# design.net
KiCad netlist of a schematic drawn in Altium Designer
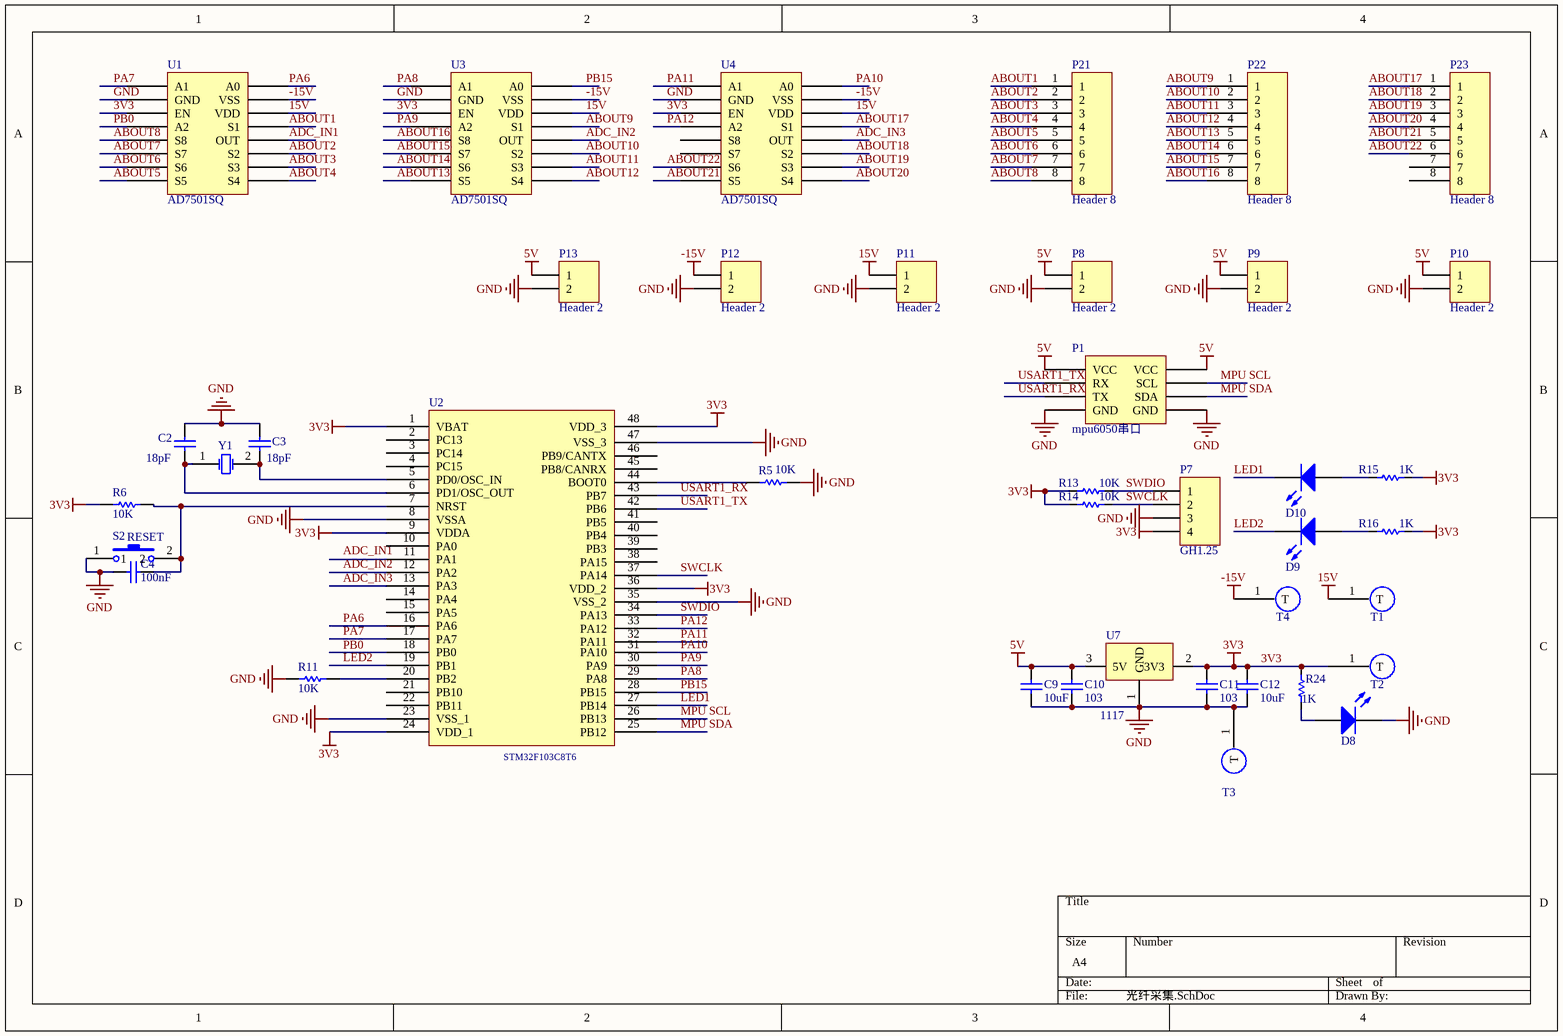
[diagram p0: 光纤采集.SchDoc]

(export (version "E")
  (design (tool "Eeschema 10.0.6"))
  (components
    (comp (ref "C2")
      (value "18pF")
      (footprint "0402")
      (description "Capacitor")
      (fields (field (name "Comment") "Cap") (field (name "PUBLISHER") "Altium Limited"))
      (libsource (lib "Miscellaneous Devices") (part "Cap"))
    )
    (comp (ref "C3")
      (value "18pF")
      (footprint "0402")
      (description "Capacitor")
      (fields (field (name "Comment") "Cap") (field (name "PUBLISHER") "Altium Limited"))
      (libsource (lib "Miscellaneous Devices") (part "Cap"))
    )
    (comp (ref "C4")
      (value "100nF")
      (footprint "0402")
      (description "Capacitor")
      (fields (field (name "Comment") "Cap") (field (name "PUBLISHER") "Altium Limited"))
      (libsource (lib "Miscellaneous Devices") (part "Cap"))
    )
    (comp (ref "C9")
      (value "10uF")
      (footprint "0603-1")
      (description "无极性电容")
      (fields (field (name "PUBLISHER") "Altium Limited"))
      (libsource (lib "Devices") (part "Cap"))
    )
    (comp (ref "C10")
      (value "103")
      (footprint "0603-1")
      (description "无极性电容")
      (fields (field (name "PUBLISHER") "Altium Limited"))
      (libsource (lib "Devices") (part "Cap"))
    )
    (comp (ref "C11")
      (value "103")
      (footprint "0603-1")
      (description "无极性电容")
      (fields (field (name "PUBLISHER") "Altium Limited"))
      (libsource (lib "Devices") (part "Cap"))
    )
    (comp (ref "C12")
      (value "10uF")
      (footprint "0603-1")
      (description "无极性电容")
      (fields (field (name "PUBLISHER") "Altium Limited"))
      (libsource (lib "Devices") (part "Cap"))
    )
    (comp (ref "D8")
      (value "LED0")
      (footprint "0603-LED-1")
      (description "发光二极管")
      (fields (field (name "PUBLISHER") "Altium Limited"))
      (libsource (lib "Devices") (part "LED0"))
    )
    (comp (ref "D9")
      (value "LED0")
      (footprint "0603-LED-1")
      (description "发光二极管")
      (fields (field (name "PUBLISHER") "Altium Limited"))
      (libsource (lib "Devices") (part "LED0"))
    )
    (comp (ref "D10")
      (value "LED0")
      (footprint "0603-LED-1")
      (description "发光二极管")
      (fields (field (name "PUBLISHER") "Altium Limited"))
      (libsource (lib "Devices") (part "LED0"))
    )
    (comp (ref "P1") (value "mpu6050串口") (footprint "MPU6050") (libsource (lib "新云台") (part "mpu6050串口")))
    (comp (ref "P7")
      (value "GH1.25")
      (footprint "GH1.25_4P")
      (description "Header, 4-Pin")
      (fields (field (name "PUBLISHER") "Altium Limited"))
      (libsource (lib "继电器") (part "Header 4"))
    )
    (comp (ref "P8")
      (value "Header 2")
      (footprint "2.54x2")
      (description "Header, 2-Pin")
      (fields (field (name "PUBLISHER") "Altium Limited"))
      (libsource (lib "Miscellaneous Connectors") (part "Header 2"))
    )
    (comp (ref "P9")
      (value "Header 2")
      (footprint "2.54x2")
      (description "Header, 2-Pin")
      (fields (field (name "PUBLISHER") "Altium Limited"))
      (libsource (lib "Miscellaneous Connectors") (part "Header 2"))
    )
    (comp (ref "P10")
      (value "Header 2")
      (footprint "2.54x2")
      (description "Header, 2-Pin")
      (fields (field (name "PUBLISHER") "Altium Limited"))
      (libsource (lib "Miscellaneous Connectors") (part "Header 2"))
    )
    (comp (ref "P11")
      (value "Header 2")
      (footprint "2.54x2")
      (description "Header, 2-Pin")
      (fields (field (name "PUBLISHER") "Altium Limited"))
      (libsource (lib "Miscellaneous Connectors") (part "Header 2"))
    )
    (comp (ref "P12")
      (value "Header 2")
      (footprint "2.54x2")
      (description "Header, 2-Pin")
      (fields (field (name "PUBLISHER") "Altium Limited"))
      (libsource (lib "Miscellaneous Connectors") (part "Header 2"))
    )
    (comp (ref "P13")
      (value "Header 2")
      (footprint "2.54x2")
      (description "Header, 2-Pin")
      (fields (field (name "PUBLISHER") "Altium Limited"))
      (libsource (lib "Miscellaneous Connectors") (part "Header 2"))
    )
    (comp (ref "P21") (value "Header 8") (footprint "2.54x8") (libsource (lib "继电器") (part "Header 8")))
    (comp (ref "P22") (value "Header 8") (footprint "2.54x8") (libsource (lib "继电器") (part "Header 8")))
    (comp (ref "P23") (value "Header 8") (footprint "2.54x8") (libsource (lib "继电器") (part "Header 8")))
    (comp (ref "R5")
      (value "10K")
      (footprint "0402")
      (description "Semiconductor Resistor")
      (fields (field (name "Comment") "Res Semi") (field (name "PUBLISHER") "Altium Limited"))
      (libsource (lib "Miscellaneous Devices") (part "Res Semi"))
    )
    (comp (ref "R6")
      (value "10K")
      (footprint "0402")
      (description "Semiconductor Resistor")
      (fields (field (name "Comment") "Res Semi") (field (name "PUBLISHER") "Altium Limited"))
      (libsource (lib "Miscellaneous Devices") (part "Res Semi"))
    )
    (comp (ref "R11")
      (value "10K")
      (footprint "0402")
      (description "Semiconductor Resistor")
      (fields (field (name "Comment") "Res Semi") (field (name "PUBLISHER") "Altium Limited"))
      (libsource (lib "Miscellaneous Devices") (part "Res Semi"))
    )
    (comp (ref "R13")
      (value "10K")
      (footprint "0402")
      (description "贴片电阻")
      (fields (field (name "PUBLISHER") "Altium Limited"))
      (libsource (lib "继电器") (part "Res1"))
    )
    (comp (ref "R14")
      (value "10K")
      (footprint "0402")
      (description "贴片电阻")
      (fields (field (name "PUBLISHER") "Altium Limited"))
      (libsource (lib "继电器") (part "Res1"))
    )
    (comp (ref "R15")
      (value "1K")
      (footprint "0402")
      (description "贴片电阻")
      (fields (field (name "PUBLISHER") "Altium Limited"))
      (libsource (lib "继电器") (part "Res1"))
    )
    (comp (ref "R16")
      (value "1K")
      (footprint "0402")
      (description "贴片电阻")
      (fields (field (name "PUBLISHER") "Altium Limited"))
      (libsource (lib "继电器") (part "Res1"))
    )
    (comp (ref "R24")
      (value "1K")
      (footprint "0402")
      (description "贴片电阻")
      (fields (field (name "PUBLISHER") "Altium Limited"))
      (libsource (lib "Devices") (part "Res1"))
    )
    (comp (ref "S2")
      (value "RESET")
      (footprint "KEY 4P")
      (description "微动开关")
      (fields (field (name "PUBLISHER") "Altium Limited"))
      (libsource (lib "Devices") (part "SW-PB"))
    )
    (comp (ref "T1") (value "~") (footprint "Test") (libsource (lib "PTZ") (part "TEST")))
    (comp (ref "T2") (value "~") (footprint "Test") (libsource (lib "PTZ") (part "TEST")))
    (comp (ref "T3") (value "~") (footprint "Test") (libsource (lib "PTZ") (part "TEST")))
    (comp (ref "T4") (value "~") (footprint "Test") (libsource (lib "PTZ") (part "TEST")))
    (comp (ref "U1") (value "AD7501SQ") (footprint "DIP-16") (libsource (lib "新云台") (part "AD7501SQ")))
    (comp (ref "U2")
      (value "STM32F103C8T6")
      (footprint "LQFP48_stm32f103_")
      (libsource (lib "driver") (part "STM32F103C8T6"))
    )
    (comp (ref "U3") (value "AD7501SQ") (footprint "DIP-16") (libsource (lib "新云台") (part "AD7501SQ")))
    (comp (ref "U4") (value "AD7501SQ") (footprint "DIP-16") (libsource (lib "新云台") (part "AD7501SQ")))
    (comp (ref "U7")
      (value "1117")
      (footprint "SOT223_1117__")
      (libsource (lib "SHAWN") (part "AMS1117-3.3"))
    )
    (comp (ref "Y1")
      (value "XTAL")
      (footprint "XTAL5032")
      (description "Crystal Oscillator")
      (fields (field (name "PUBLISHER") "Altium Limited"))
      (libsource (lib "Miscellaneous Devices") (part "XTAL"))
    )
  )
  (nets
    (net (code "1") (name "-15V") (class "Default")
      (node (ref "P12") (pin "1") (pinfunction "1_1") (pintype "passive"))
      (node (ref "T4") (pin "1") (pinfunction "T_1") (pintype "passive"))
      (node (ref "U1") (pin "14") (pinfunction "VSS_14") (pintype "passive"))
      (node (ref "U3") (pin "14") (pinfunction "VSS_14") (pintype "passive"))
      (node (ref "U4") (pin "14") (pinfunction "VSS_14") (pintype "passive"))
    )
    (net (code "2") (name "/ABOUT1") (class "Default")
      (node (ref "P21") (pin "1") (pinfunction "1_1") (pintype "passive"))
      (node (ref "U1") (pin "12") (pinfunction "S1_12") (pintype "passive"))
    )
    (net (code "3") (name "/ABOUT2") (class "Default")
      (node (ref "P21") (pin "2") (pinfunction "2_2") (pintype "passive"))
      (node (ref "U1") (pin "11") (pinfunction "S2_11") (pintype "passive"))
    )
    (net (code "4") (name "/ABOUT3") (class "Default")
      (node (ref "P21") (pin "3") (pinfunction "3_3") (pintype "passive"))
      (node (ref "U1") (pin "10") (pinfunction "S3_10") (pintype "passive"))
    )
    (net (code "5") (name "/ABOUT4") (class "Default")
      (node (ref "P21") (pin "4") (pinfunction "4_4") (pintype "passive"))
      (node (ref "U1") (pin "9") (pinfunction "S4_9") (pintype "passive"))
    )
    (net (code "6") (name "/ABOUT5") (class "Default")
      (node (ref "P21") (pin "5") (pinfunction "5_5") (pintype "passive"))
      (node (ref "U1") (pin "8") (pinfunction "S5_8") (pintype "passive"))
    )
    (net (code "7") (name "/ABOUT6") (class "Default")
      (node (ref "P21") (pin "6") (pinfunction "6_6") (pintype "passive"))
      (node (ref "U1") (pin "7") (pinfunction "S6_7") (pintype "passive"))
    )
    (net (code "8") (name "/ABOUT7") (class "Default")
      (node (ref "P21") (pin "7") (pinfunction "7_7") (pintype "passive"))
      (node (ref "U1") (pin "6") (pinfunction "S7_6") (pintype "passive"))
    )
    (net (code "9") (name "/ABOUT8") (class "Default")
      (node (ref "P21") (pin "8") (pinfunction "8_8") (pintype "passive"))
      (node (ref "U1") (pin "5") (pinfunction "S8_5") (pintype "passive"))
    )
    (net (code "10") (name "/ABOUT9") (class "Default")
      (node (ref "P22") (pin "1") (pinfunction "1_1") (pintype "passive"))
      (node (ref "U3") (pin "12") (pinfunction "S1_12") (pintype "passive"))
    )
    (net (code "11") (name "/ABOUT10") (class "Default")
      (node (ref "P22") (pin "2") (pinfunction "2_2") (pintype "passive"))
      (node (ref "U3") (pin "11") (pinfunction "S2_11") (pintype "passive"))
    )
    (net (code "12") (name "/ABOUT11") (class "Default")
      (node (ref "P22") (pin "3") (pinfunction "3_3") (pintype "passive"))
      (node (ref "U3") (pin "10") (pinfunction "S3_10") (pintype "passive"))
    )
    (net (code "13") (name "/ABOUT12") (class "Default")
      (node (ref "P22") (pin "4") (pinfunction "4_4") (pintype "passive"))
      (node (ref "U3") (pin "9") (pinfunction "S4_9") (pintype "passive"))
    )
    (net (code "14") (name "/ABOUT13") (class "Default")
      (node (ref "P22") (pin "5") (pinfunction "5_5") (pintype "passive"))
      (node (ref "U3") (pin "8") (pinfunction "S5_8") (pintype "passive"))
    )
    (net (code "15") (name "/ABOUT14") (class "Default")
      (node (ref "P22") (pin "6") (pinfunction "6_6") (pintype "passive"))
      (node (ref "U3") (pin "7") (pinfunction "S6_7") (pintype "passive"))
    )
    (net (code "16") (name "/ABOUT15") (class "Default")
      (node (ref "P22") (pin "7") (pinfunction "7_7") (pintype "passive"))
      (node (ref "U3") (pin "6") (pinfunction "S7_6") (pintype "passive"))
    )
    (net (code "17") (name "/ABOUT16") (class "Default")
      (node (ref "P22") (pin "8") (pinfunction "8_8") (pintype "passive"))
      (node (ref "U3") (pin "5") (pinfunction "S8_5") (pintype "passive"))
    )
    (net (code "18") (name "/ABOUT17") (class "Default")
      (node (ref "P23") (pin "1") (pinfunction "1_1") (pintype "passive"))
      (node (ref "U4") (pin "12") (pinfunction "S1_12") (pintype "passive"))
    )
    (net (code "19") (name "/ABOUT18") (class "Default")
      (node (ref "P23") (pin "2") (pinfunction "2_2") (pintype "passive"))
      (node (ref "U4") (pin "11") (pinfunction "S2_11") (pintype "passive"))
    )
    (net (code "20") (name "/ABOUT19") (class "Default")
      (node (ref "P23") (pin "3") (pinfunction "3_3") (pintype "passive"))
      (node (ref "U4") (pin "10") (pinfunction "S3_10") (pintype "passive"))
    )
    (net (code "21") (name "/ABOUT20") (class "Default")
      (node (ref "P23") (pin "4") (pinfunction "4_4") (pintype "passive"))
      (node (ref "U4") (pin "9") (pinfunction "S4_9") (pintype "passive"))
    )
    (net (code "22") (name "/ABOUT21") (class "Default")
      (node (ref "P23") (pin "5") (pinfunction "5_5") (pintype "passive"))
      (node (ref "U4") (pin "8") (pinfunction "S5_8") (pintype "passive"))
    )
    (net (code "23") (name "/ABOUT22") (class "Default")
      (node (ref "P23") (pin "6") (pinfunction "6_6") (pintype "passive"))
      (node (ref "U4") (pin "7") (pinfunction "S6_7") (pintype "passive"))
    )
    (net (code "24") (name "/ADC_IN1") (class "Default")
      (node (ref "U1") (pin "12") (pinfunction "OUT_12") (pintype "passive"))
    )
    (net (code "25") (name "/ADC_IN2") (class "Default")
      (node (ref "U3") (pin "12") (pinfunction "OUT_12") (pintype "passive"))
    )
    (net (code "26") (name "/ADC_IN3") (class "Default")
      (node (ref "U2") (pin "13") (pinfunction "PA3_13") (pintype "passive"))
      (node (ref "U4") (pin "12") (pinfunction "OUT_12") (pintype "passive"))
    )
    (net (code "27") (name "/LED1") (class "Default")
      (node (ref "D10") (pin "2") (pinfunction "K_2") (pintype "passive"))
      (node (ref "U2") (pin "27") (pinfunction "PB14_27") (pintype "passive"))
    )
    (net (code "28") (name "/LED2") (class "Default")
      (node (ref "D9") (pin "2") (pinfunction "K_2") (pintype "passive"))
      (node (ref "U2") (pin "19") (pinfunction "PB1_19") (pintype "passive"))
    )
    (net (code "29") (name "/MPU SCL") (class "Default")
      (node (ref "P1") (pin "7") (pinfunction "SCL_7") (pintype "passive"))
      (node (ref "U2") (pin "26") (pinfunction "PB13_26") (pintype "passive"))
    )
    (net (code "30") (name "/MPU SDA") (class "Default")
      (node (ref "P1") (pin "6") (pinfunction "SDA_6") (pintype "passive"))
      (node (ref "U2") (pin "25") (pinfunction "PB12_25") (pintype "passive"))
    )
    (net (code "31") (name "/PA6") (class "Default")
      (node (ref "U1") (pin "15") (pinfunction "A0_15") (pintype "passive"))
      (node (ref "U2") (pin "16") (pinfunction "PA6_16") (pintype "passive"))
    )
    (net (code "32") (name "/PA7") (class "Default")
      (node (ref "U1") (pin "1") (pinfunction "A1_1") (pintype "passive"))
      (node (ref "U2") (pin "17") (pinfunction "PA7_17") (pintype "passive"))
    )
    (net (code "33") (name "/PA8") (class "Default")
      (node (ref "U2") (pin "29") (pinfunction "PA8_29") (pintype "passive"))
      (node (ref "U3") (pin "1") (pinfunction "A1_1") (pintype "passive"))
    )
    (net (code "34") (name "/PA9") (class "Default")
      (node (ref "U2") (pin "30") (pinfunction "PA9_30") (pintype "passive"))
      (node (ref "U3") (pin "4") (pinfunction "A2_4") (pintype "passive"))
    )
    (net (code "35") (name "/PA10") (class "Default")
      (node (ref "U2") (pin "31") (pinfunction "PA10_31") (pintype "passive"))
      (node (ref "U4") (pin "15") (pinfunction "A0_15") (pintype "passive"))
    )
    (net (code "36") (name "/PA11") (class "Default")
      (node (ref "U2") (pin "32") (pinfunction "PA11_32") (pintype "passive"))
      (node (ref "U4") (pin "1") (pinfunction "A1_1") (pintype "passive"))
    )
    (net (code "37") (name "/PA12") (class "Default")
      (node (ref "U2") (pin "33") (pinfunction "PA12_33") (pintype "passive"))
      (node (ref "U4") (pin "4") (pinfunction "A2_4") (pintype "passive"))
    )
    (net (code "38") (name "/PB0") (class "Default")
      (node (ref "U1") (pin "4") (pinfunction "A2_4") (pintype "passive"))
    )
    (net (code "39") (name "/PB15") (class "Default")
      (node (ref "U2") (pin "28") (pinfunction "PB15_28") (pintype "passive"))
      (node (ref "U3") (pin "15") (pinfunction "A0_15") (pintype "passive"))
    )
    (net (code "40") (name "/SWCLK") (class "Default")
      (node (ref "P7") (pin "2") (pinfunction "2_2") (pintype "passive"))
      (node (ref "R14") (pin "2") (pinfunction "BOT_2") (pintype "passive"))
      (node (ref "U2") (pin "37") (pinfunction "PA14_37") (pintype "passive"))
    )
    (net (code "41") (name "/SWDIO") (class "Default")
      (node (ref "P7") (pin "1") (pinfunction "1_1") (pintype "passive"))
      (node (ref "R13") (pin "2") (pinfunction "BOT_2") (pintype "passive"))
      (node (ref "U2") (pin "34") (pinfunction "PA13_34") (pintype "passive"))
    )
    (net (code "42") (name "/USART1_RX") (class "Default")
      (node (ref "P1") (pin "3") (pinfunction "TX_3") (pintype "passive"))
      (node (ref "U2") (pin "43") (pinfunction "PB7_43") (pintype "passive"))
    )
    (net (code "43") (name "/USART1_TX") (class "Default")
      (node (ref "P1") (pin "2") (pinfunction "RX_2") (pintype "passive"))
      (node (ref "U2") (pin "42") (pinfunction "PB6_42") (pintype "passive"))
    )
    (net (code "44") (name "3V3") (class "Default")
      (node (ref "C11") (pin "2") (pinfunction "2_2") (pintype "passive"))
      (node (ref "C12") (pin "2") (pinfunction "2_2") (pintype "passive"))
      (node (ref "P7") (pin "4") (pinfunction "4_4") (pintype "passive"))
      (node (ref "R13") (pin "1") (pinfunction "TOP_1") (pintype "passive"))
      (node (ref "R14") (pin "1") (pinfunction "TOP_1") (pintype "passive"))
      (node (ref "R15") (pin "2") (pinfunction "BOT_2") (pintype "passive"))
      (node (ref "R16") (pin "2") (pinfunction "BOT_2") (pintype "passive"))
      (node (ref "R24") (pin "1") (pinfunction "TOP_1") (pintype "passive"))
      (node (ref "R6") (pin "2") (pinfunction "2_2") (pintype "passive"))
      (node (ref "T2") (pin "1") (pinfunction "T_1") (pintype "passive"))
      (node (ref "U1") (pin "3") (pinfunction "EN_3") (pintype "passive"))
      (node (ref "U2") (pin "1") (pinfunction "VBAT_1") (pintype "passive"))
      (node (ref "U2") (pin "24") (pinfunction "VDD_1_24") (pintype "passive"))
      (node (ref "U2") (pin "36") (pinfunction "VDD_2_36") (pintype "passive"))
      (node (ref "U2") (pin "48") (pinfunction "VDD_3_48") (pintype "passive"))
      (node (ref "U2") (pin "9") (pinfunction "VDDA_9") (pintype "passive"))
      (node (ref "U3") (pin "3") (pinfunction "EN_3") (pintype "passive"))
      (node (ref "U4") (pin "3") (pinfunction "EN_3") (pintype "passive"))
      (node (ref "U7") (pin "2") (pinfunction "3V3_2") (pintype "passive"))
    )
    (net (code "45") (name "5V") (class "Default")
      (node (ref "C10") (pin "2") (pinfunction "2_2") (pintype "passive"))
      (node (ref "C9") (pin "2") (pinfunction "2_2") (pintype "passive"))
      (node (ref "P1") (pin "1") (pinfunction "VCC_1") (pintype "passive"))
      (node (ref "P1") (pin "8") (pinfunction "VCC_8") (pintype "passive"))
      (node (ref "P10") (pin "1") (pinfunction "1_1") (pintype "passive"))
      (node (ref "P13") (pin "1") (pinfunction "1_1") (pintype "passive"))
      (node (ref "P8") (pin "1") (pinfunction "1_1") (pintype "passive"))
      (node (ref "P9") (pin "1") (pinfunction "1_1") (pintype "passive"))
      (node (ref "U7") (pin "3") (pinfunction "5V_3") (pintype "passive"))
    )
    (net (code "46") (name "15V") (class "Default")
      (node (ref "P11") (pin "1") (pinfunction "1_1") (pintype "passive"))
      (node (ref "T1") (pin "1") (pinfunction "T_1") (pintype "passive"))
      (node (ref "U1") (pin "13") (pinfunction "VDD_13") (pintype "passive"))
      (node (ref "U3") (pin "13") (pinfunction "VDD_13") (pintype "passive"))
      (node (ref "U4") (pin "13") (pinfunction "VDD_13") (pintype "passive"))
    )
    (net (code "47") (name "GND") (class "Default")
      (node (ref "C10") (pin "1") (pinfunction "1_1") (pintype "passive"))
      (node (ref "C11") (pin "1") (pinfunction "1_1") (pintype "passive"))
      (node (ref "C12") (pin "1") (pinfunction "1_1") (pintype "passive"))
      (node (ref "C2") (pin "2") (pinfunction "2_2") (pintype "passive"))
      (node (ref "C3") (pin "2") (pinfunction "2_2") (pintype "passive"))
      (node (ref "C4") (pin "2") (pinfunction "2_2") (pintype "passive"))
      (node (ref "C9") (pin "1") (pinfunction "1_1") (pintype "passive"))
      (node (ref "D8") (pin "2") (pinfunction "K_2") (pintype "passive"))
      (node (ref "P1") (pin "4") (pinfunction "GND_4") (pintype "passive"))
      (node (ref "P1") (pin "5") (pinfunction "GND_5") (pintype "passive"))
      (node (ref "P10") (pin "2") (pinfunction "2_2") (pintype "passive"))
      (node (ref "P11") (pin "2") (pinfunction "2_2") (pintype "passive"))
      (node (ref "P12") (pin "2") (pinfunction "2_2") (pintype "passive"))
      (node (ref "P13") (pin "2") (pinfunction "2_2") (pintype "passive"))
      (node (ref "P7") (pin "3") (pinfunction "3_3") (pintype "passive"))
      (node (ref "P8") (pin "2") (pinfunction "2_2") (pintype "passive"))
      (node (ref "P9") (pin "2") (pinfunction "2_2") (pintype "passive"))
      (node (ref "R11") (pin "1") (pinfunction "1_1") (pintype "passive"))
      (node (ref "R5") (pin "2") (pinfunction "2_2") (pintype "passive"))
      (node (ref "S2") (pin "1") (pinfunction "1_1") (pintype "passive"))
      (node (ref "T3") (pin "1") (pinfunction "T_1") (pintype "passive"))
      (node (ref "U1") (pin "2") (pinfunction "GND_2") (pintype "passive"))
      (node (ref "U2") (pin "23") (pinfunction "VSS_1_23") (pintype "passive"))
      (node (ref "U2") (pin "35") (pinfunction "VSS_2_35") (pintype "passive"))
      (node (ref "U2") (pin "47") (pinfunction "VSS_3_47") (pintype "passive"))
      (node (ref "U2") (pin "8") (pinfunction "VSSA_8") (pintype "passive"))
      (node (ref "U3") (pin "2") (pinfunction "GND_2") (pintype "passive"))
      (node (ref "U4") (pin "2") (pinfunction "GND_2") (pintype "passive"))
      (node (ref "U7") (pin "1") (pinfunction "GND_1") (pintype "passive"))
    )
    (net (code "48") (name "Net-(D8-A)") (class "Default")
      (node (ref "D8") (pin "1") (pinfunction "A_1") (pintype "passive"))
      (node (ref "R24") (pin "2") (pinfunction "BOT_2") (pintype "passive"))
    )
    (net (code "49") (name "Net-(D9-A)") (class "Default")
      (node (ref "D9") (pin "1") (pinfunction "A_1") (pintype "passive"))
      (node (ref "R16") (pin "1") (pinfunction "TOP_1") (pintype "passive"))
    )
    (net (code "50") (name "Net-(D10-A)") (class "Default")
      (node (ref "D10") (pin "1") (pinfunction "A_1") (pintype "passive"))
      (node (ref "R15") (pin "1") (pinfunction "TOP_1") (pintype "passive"))
    )
    (net (code "51") (name "Net-(U2-BOOT0)") (class "Default")
      (node (ref "R5") (pin "1") (pinfunction "1_1") (pintype "passive"))
      (node (ref "U2") (pin "44") (pinfunction "BOOT0_44") (pintype "passive"))
    )
    (net (code "52") (name "Net-(U2-NRST)") (class "Default")
      (node (ref "C4") (pin "1") (pinfunction "1_1") (pintype "passive"))
      (node (ref "R6") (pin "1") (pinfunction "1_1") (pintype "passive"))
      (node (ref "S2") (pin "2") (pinfunction "2_2") (pintype "passive"))
      (node (ref "U2") (pin "7") (pinfunction "NRST_7") (pintype "passive"))
    )
    (net (code "53") (name "Net-(U2-PB2)") (class "Default")
      (node (ref "R11") (pin "2") (pinfunction "2_2") (pintype "passive"))
      (node (ref "U2") (pin "20") (pinfunction "PB2_20") (pintype "passive"))
    )
    (net (code "54") (name "Net-(U2-PD0{slash}OSC_IN)") (class "Default")
      (node (ref "C3") (pin "1") (pinfunction "1_1") (pintype "passive"))
      (node (ref "U2") (pin "5") (pinfunction "PD0/OSC_IN_5") (pintype "passive"))
      (node (ref "Y1") (pin "2") (pinfunction "OSC2_2") (pintype "passive"))
    )
    (net (code "55") (name "Net-(U2-PD1{slash}OSC_OUT)") (class "Default")
      (node (ref "C2") (pin "1") (pinfunction "1_1") (pintype "passive"))
      (node (ref "U2") (pin "6") (pinfunction "PD1/OSC_OUT_6") (pintype "passive"))
      (node (ref "Y1") (pin "1") (pinfunction "OSC1_1") (pintype "passive"))
    )
    (net (code "56") (name "unconnected-(P23-Pad7)") (class "Default")
      (node (ref "P23") (pin "7") (pinfunction "7_7") (pintype "passive"))
    )
    (net (code "57") (name "unconnected-(P23-Pad8)") (class "Default")
      (node (ref "P23") (pin "8") (pinfunction "8_8") (pintype "passive"))
    )
    (net (code "58") (name "unconnected-(U2-PA0-Pad10)") (class "Default")
      (node (ref "U2") (pin "10") (pinfunction "PA0_10") (pintype "passive"))
    )
    (net (code "59") (name "unconnected-(U2-PA1-Pad11)") (class "Default")
      (node (ref "U2") (pin "11") (pinfunction "PA1_11") (pintype "passive"))
    )
    (net (code "60") (name "unconnected-(U2-PA2-Pad12)") (class "Default")
      (node (ref "U2") (pin "12") (pinfunction "PA2_12") (pintype "passive"))
    )
    (net (code "61") (name "unconnected-(U2-PA4-Pad14)") (class "Default")
      (node (ref "U2") (pin "14") (pinfunction "PA4_14") (pintype "passive"))
    )
    (net (code "62") (name "unconnected-(U2-PA5-Pad15)") (class "Default")
      (node (ref "U2") (pin "15") (pinfunction "PA5_15") (pintype "passive"))
    )
    (net (code "63") (name "unconnected-(U2-PA15-Pad38)") (class "Default")
      (node (ref "U2") (pin "38") (pinfunction "PA15_38") (pintype "passive"))
    )
    (net (code "64") (name "unconnected-(U2-PB0-Pad18)") (class "Default")
      (node (ref "U2") (pin "18") (pinfunction "PB0_18") (pintype "passive"))
    )
    (net (code "65") (name "unconnected-(U2-PB3-Pad39)") (class "Default")
      (node (ref "U2") (pin "39") (pinfunction "PB3_39") (pintype "passive"))
    )
    (net (code "66") (name "unconnected-(U2-PB4-Pad40)") (class "Default")
      (node (ref "U2") (pin "40") (pinfunction "PB4_40") (pintype "passive"))
    )
    (net (code "67") (name "unconnected-(U2-PB5-Pad41)") (class "Default")
      (node (ref "U2") (pin "41") (pinfunction "PB5_41") (pintype "passive"))
    )
    (net (code "68") (name "unconnected-(U2-PB8{slash}CANRX-Pad45)") (class "Default")
      (node (ref "U2") (pin "45") (pinfunction "PB8/CANRX_45") (pintype "passive"))
    )
    (net (code "69") (name "unconnected-(U2-PB9{slash}CANTX-Pad46)") (class "Default")
      (node (ref "U2") (pin "46") (pinfunction "PB9/CANTX_46") (pintype "passive"))
    )
    (net (code "70") (name "unconnected-(U2-PB10-Pad21)") (class "Default")
      (node (ref "U2") (pin "21") (pinfunction "PB10_21") (pintype "passive"))
    )
    (net (code "71") (name "unconnected-(U2-PB11-Pad22)") (class "Default")
      (node (ref "U2") (pin "22") (pinfunction "PB11_22") (pintype "passive"))
    )
    (net (code "72") (name "unconnected-(U2-PC13-Pad2)") (class "Default")
      (node (ref "U2") (pin "2") (pinfunction "PC13_2") (pintype "passive"))
    )
    (net (code "73") (name "unconnected-(U2-PC14-Pad3)") (class "Default")
      (node (ref "U2") (pin "3") (pinfunction "PC14_3") (pintype "passive"))
    )
    (net (code "74") (name "unconnected-(U2-PC15-Pad4)") (class "Default")
      (node (ref "U2") (pin "4") (pinfunction "PC15_4") (pintype "passive"))
    )
    (net (code "75") (name "unconnected-(U4-S7-Pad6)") (class "Default")
      (node (ref "U4") (pin "6") (pinfunction "S7_6") (pintype "passive"))
    )
    (net (code "76") (name "unconnected-(U4-S8-Pad5)") (class "Default")
      (node (ref "U4") (pin "5") (pinfunction "S8_5") (pintype "passive"))
    )
  )
)
